# Protoboard.net
KiCad netlist of a schematic drawn in Altium Designer
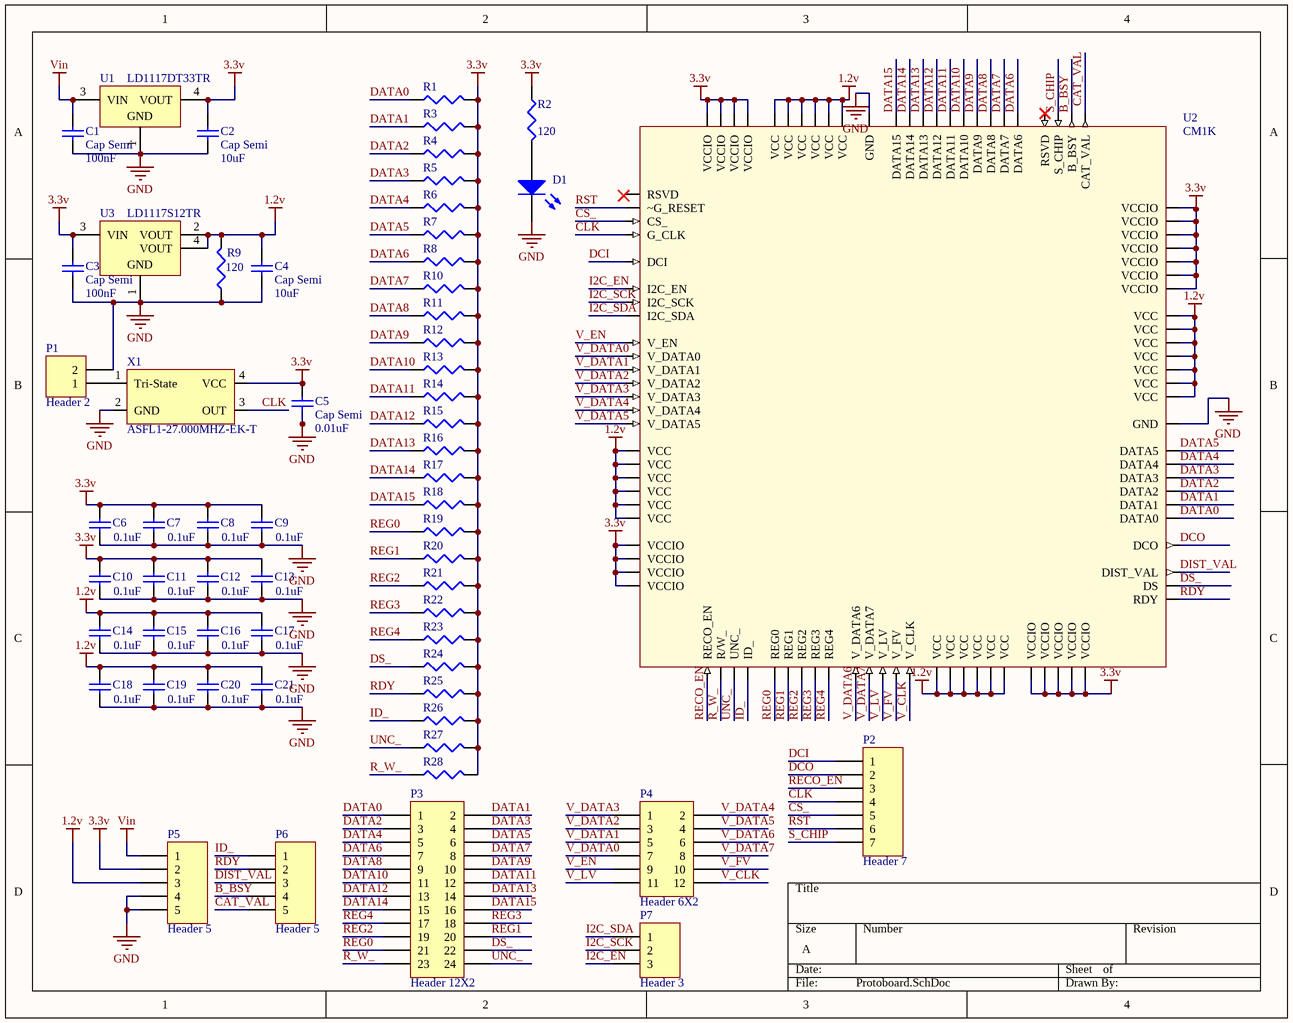
[diagram p0: Protoboard.SchDoc]

(export (version "E")
  (design (tool "Eeschema 10.0.6"))
  (components
    (comp (ref "C1")
      (value "Cap Semi")
      (footprint "1608[0603]")
      (description "Capacitor (Semiconductor SIM Model)")
      (fields (field (name "ALTIUM_VALUE") "100nF") (field (name "PUBLISHER") "Altium Limited"))
      (libsource (lib "Miscellaneous Devices") (part "Cap Semi"))
    )
    (comp (ref "C2")
      (value "Cap Semi")
      (footprint "1608[0603]")
      (description "Capacitor (Semiconductor SIM Model)")
      (fields (field (name "ALTIUM_VALUE") "10uF") (field (name "PUBLISHER") "Altium Limited"))
      (libsource (lib "Miscellaneous Devices") (part "Cap Semi"))
    )
    (comp (ref "C3")
      (value "Cap Semi")
      (footprint "1608[0603]")
      (description "Capacitor (Semiconductor SIM Model)")
      (fields (field (name "ALTIUM_VALUE") "100nF") (field (name "PUBLISHER") "Altium Limited"))
      (libsource (lib "Miscellaneous Devices") (part "Cap Semi"))
    )
    (comp (ref "C4")
      (value "Cap Semi")
      (footprint "1608[0603]")
      (description "Capacitor (Semiconductor SIM Model)")
      (fields (field (name "ALTIUM_VALUE") "10uF") (field (name "PUBLISHER") "Altium Limited"))
      (libsource (lib "Miscellaneous Devices") (part "Cap Semi"))
    )
    (comp (ref "C5")
      (value "Cap Semi")
      (footprint "1608[0603]")
      (description "Capacitor (Semiconductor SIM Model)")
      (fields (field (name "ALTIUM_VALUE") "0.01uF") (field (name "PUBLISHER") "Altium Limited"))
      (libsource (lib "Miscellaneous Devices") (part "Cap Semi"))
    )
    (comp (ref "C6")
      (value "0.1uF")
      (footprint "1608[0603]")
      (description "Capacitor (Semiconductor SIM Model)")
      (fields (field (name "Comment") "Cap Semi") (field (name "PUBLISHER") "Altium Limited"))
      (libsource (lib "Miscellaneous Devices") (part "Cap Semi"))
    )
    (comp (ref "C7")
      (value "0.1uF")
      (footprint "1608[0603]")
      (description "Capacitor (Semiconductor SIM Model)")
      (fields (field (name "Comment") "Cap Semi") (field (name "PUBLISHER") "Altium Limited"))
      (libsource (lib "Miscellaneous Devices") (part "Cap Semi"))
    )
    (comp (ref "C8")
      (value "0.1uF")
      (footprint "1608[0603]")
      (description "Capacitor (Semiconductor SIM Model)")
      (fields (field (name "Comment") "Cap Semi") (field (name "PUBLISHER") "Altium Limited"))
      (libsource (lib "Miscellaneous Devices") (part "Cap Semi"))
    )
    (comp (ref "C9")
      (value "0.1uF")
      (footprint "1608[0603]")
      (description "Capacitor (Semiconductor SIM Model)")
      (fields (field (name "Comment") "Cap Semi") (field (name "PUBLISHER") "Altium Limited"))
      (libsource (lib "Miscellaneous Devices") (part "Cap Semi"))
    )
    (comp (ref "C10")
      (value "0.1uF")
      (footprint "1608[0603]")
      (description "Capacitor (Semiconductor SIM Model)")
      (fields (field (name "Comment") "Cap Semi") (field (name "PUBLISHER") "Altium Limited"))
      (libsource (lib "Miscellaneous Devices") (part "Cap Semi"))
    )
    (comp (ref "C11")
      (value "0.1uF")
      (footprint "1608[0603]")
      (description "Capacitor (Semiconductor SIM Model)")
      (fields (field (name "Comment") "Cap Semi") (field (name "PUBLISHER") "Altium Limited"))
      (libsource (lib "Miscellaneous Devices") (part "Cap Semi"))
    )
    (comp (ref "C12")
      (value "0.1uF")
      (footprint "1608[0603]")
      (description "Capacitor (Semiconductor SIM Model)")
      (fields (field (name "Comment") "Cap Semi") (field (name "PUBLISHER") "Altium Limited"))
      (libsource (lib "Miscellaneous Devices") (part "Cap Semi"))
    )
    (comp (ref "C13")
      (value "0.1uF")
      (footprint "1608[0603]")
      (description "Capacitor (Semiconductor SIM Model)")
      (fields (field (name "Comment") "Cap Semi") (field (name "PUBLISHER") "Altium Limited"))
      (libsource (lib "Miscellaneous Devices") (part "Cap Semi"))
    )
    (comp (ref "C14")
      (value "0.1uF")
      (footprint "1608[0603]")
      (description "Capacitor (Semiconductor SIM Model)")
      (fields (field (name "Comment") "Cap Semi") (field (name "PUBLISHER") "Altium Limited"))
      (libsource (lib "Miscellaneous Devices") (part "Cap Semi"))
    )
    (comp (ref "C15")
      (value "0.1uF")
      (footprint "1608[0603]")
      (description "Capacitor (Semiconductor SIM Model)")
      (fields (field (name "Comment") "Cap Semi") (field (name "PUBLISHER") "Altium Limited"))
      (libsource (lib "Miscellaneous Devices") (part "Cap Semi"))
    )
    (comp (ref "C16")
      (value "0.1uF")
      (footprint "1608[0603]")
      (description "Capacitor (Semiconductor SIM Model)")
      (fields (field (name "Comment") "Cap Semi") (field (name "PUBLISHER") "Altium Limited"))
      (libsource (lib "Miscellaneous Devices") (part "Cap Semi"))
    )
    (comp (ref "C17")
      (value "0.1uF")
      (footprint "1608[0603]")
      (description "Capacitor (Semiconductor SIM Model)")
      (fields (field (name "Comment") "Cap Semi") (field (name "PUBLISHER") "Altium Limited"))
      (libsource (lib "Miscellaneous Devices") (part "Cap Semi"))
    )
    (comp (ref "C18")
      (value "0.1uF")
      (footprint "1608[0603]")
      (description "Capacitor (Semiconductor SIM Model)")
      (fields (field (name "Comment") "Cap Semi") (field (name "PUBLISHER") "Altium Limited"))
      (libsource (lib "Miscellaneous Devices") (part "Cap Semi"))
    )
    (comp (ref "C19")
      (value "0.1uF")
      (footprint "1608[0603]")
      (description "Capacitor (Semiconductor SIM Model)")
      (fields (field (name "Comment") "Cap Semi") (field (name "PUBLISHER") "Altium Limited"))
      (libsource (lib "Miscellaneous Devices") (part "Cap Semi"))
    )
    (comp (ref "C20")
      (value "0.1uF")
      (footprint "1608[0603]")
      (description "Capacitor (Semiconductor SIM Model)")
      (fields (field (name "Comment") "Cap Semi") (field (name "PUBLISHER") "Altium Limited"))
      (libsource (lib "Miscellaneous Devices") (part "Cap Semi"))
    )
    (comp (ref "C21")
      (value "0.1uF")
      (footprint "1608[0603]")
      (description "Capacitor (Semiconductor SIM Model)")
      (fields (field (name "Comment") "Cap Semi") (field (name "PUBLISHER") "Altium Limited"))
      (libsource (lib "Miscellaneous Devices") (part "Cap Semi"))
    )
    (comp (ref "D1")
      (value "150060BS75000")
      (footprint "0603_A")
      (description "SMD mono-color Chip LED, WL-SMCW, Blue")
      (fields (field (name "MANUFACTURER") "Wuerth Elektronik"))
      (libsource (lib "Altium Content Vault") (part "WE-LED_K1A2-2"))
    )
    (comp (ref "P1")
      (value "Header 2")
      (footprint "HDR1X2")
      (description "Header, 2-Pin")
      (fields (field (name "PUBLISHER") "Altium Limited"))
      (libsource (lib "Miscellaneous Connectors") (part "Header 2"))
    )
    (comp (ref "P2")
      (value "Header 7")
      (footprint "HDR1X7")
      (description "Header, 7-Pin")
      (fields (field (name "PUBLISHER") "Altium Limited"))
      (libsource (lib "Miscellaneous Connectors") (part "Header 7"))
    )
    (comp (ref "P3")
      (value "Header 12X2")
      (footprint "HDR2X12")
      (description "Header, 12-Pin, Dual row")
      (fields (field (name "PUBLISHER") "Altium Limited"))
      (libsource (lib "Miscellaneous Connectors") (part "Header 12X2"))
    )
    (comp (ref "P4")
      (value "Header 6X2")
      (footprint "HDR2X6")
      (description "Header, 6-Pin, Dual row")
      (fields (field (name "PUBLISHER") "Altium Limited"))
      (libsource (lib "Miscellaneous Connectors") (part "Header 6X2"))
    )
    (comp (ref "P5")
      (value "Header 5")
      (footprint "HDR1X5")
      (description "Header, 5-Pin")
      (fields (field (name "PUBLISHER") "Altium Limited"))
      (libsource (lib "Miscellaneous Connectors") (part "Header 5"))
    )
    (comp (ref "P6")
      (value "Header 5")
      (footprint "HDR1X5")
      (description "Header, 5-Pin")
      (fields (field (name "PUBLISHER") "Altium Limited"))
      (libsource (lib "Miscellaneous Connectors") (part "Header 5"))
    )
    (comp (ref "P7")
      (value "Header 3")
      (footprint "HDR1X3")
      (description "Header, 3-Pin")
      (fields (field (name "PUBLISHER") "Altium Limited"))
      (libsource (lib "Miscellaneous Connectors") (part "Header 3"))
    )
    (comp (ref "R1")
      (value "Res3")
      (footprint "J1-0603")
      (description "Resistor")
      (fields (field (name "PUBLISHER") "Altium Limited"))
      (libsource (lib "Miscellaneous Devices") (part "Res3"))
    )
    (comp (ref "R2")
      (value "120")
      (footprint "J1-0603")
      (description "Resistor")
      (fields (field (name "Comment") "Res3") (field (name "PUBLISHER") "Altium Limited"))
      (libsource (lib "Miscellaneous Devices") (part "Res3"))
    )
    (comp (ref "R3")
      (value "Res3")
      (footprint "J1-0603")
      (description "Resistor")
      (fields (field (name "PUBLISHER") "Altium Limited"))
      (libsource (lib "Miscellaneous Devices") (part "Res3"))
    )
    (comp (ref "R4")
      (value "Res3")
      (footprint "J1-0603")
      (description "Resistor")
      (fields (field (name "PUBLISHER") "Altium Limited"))
      (libsource (lib "Miscellaneous Devices") (part "Res3"))
    )
    (comp (ref "R5")
      (value "Res3")
      (footprint "J1-0603")
      (description "Resistor")
      (fields (field (name "PUBLISHER") "Altium Limited"))
      (libsource (lib "Miscellaneous Devices") (part "Res3"))
    )
    (comp (ref "R6")
      (value "Res3")
      (footprint "J1-0603")
      (description "Resistor")
      (fields (field (name "PUBLISHER") "Altium Limited"))
      (libsource (lib "Miscellaneous Devices") (part "Res3"))
    )
    (comp (ref "R7")
      (value "Res3")
      (footprint "J1-0603")
      (description "Resistor")
      (fields (field (name "PUBLISHER") "Altium Limited"))
      (libsource (lib "Miscellaneous Devices") (part "Res3"))
    )
    (comp (ref "R8")
      (value "Res3")
      (footprint "J1-0603")
      (description "Resistor")
      (fields (field (name "PUBLISHER") "Altium Limited"))
      (libsource (lib "Miscellaneous Devices") (part "Res3"))
    )
    (comp (ref "R9")
      (value "120")
      (footprint "J1-0603")
      (description "Resistor")
      (fields (field (name "Comment") "Res3") (field (name "PUBLISHER") "Altium Limited"))
      (libsource (lib "Miscellaneous Devices") (part "Res3"))
    )
    (comp (ref "R10")
      (value "Res3")
      (footprint "J1-0603")
      (description "Resistor")
      (fields (field (name "PUBLISHER") "Altium Limited"))
      (libsource (lib "Miscellaneous Devices") (part "Res3"))
    )
    (comp (ref "R11")
      (value "Res3")
      (footprint "J1-0603")
      (description "Resistor")
      (fields (field (name "PUBLISHER") "Altium Limited"))
      (libsource (lib "Miscellaneous Devices") (part "Res3"))
    )
    (comp (ref "R12")
      (value "Res3")
      (footprint "J1-0603")
      (description "Resistor")
      (fields (field (name "PUBLISHER") "Altium Limited"))
      (libsource (lib "Miscellaneous Devices") (part "Res3"))
    )
    (comp (ref "R13")
      (value "Res3")
      (footprint "J1-0603")
      (description "Resistor")
      (fields (field (name "PUBLISHER") "Altium Limited"))
      (libsource (lib "Miscellaneous Devices") (part "Res3"))
    )
    (comp (ref "R14")
      (value "Res3")
      (footprint "J1-0603")
      (description "Resistor")
      (fields (field (name "PUBLISHER") "Altium Limited"))
      (libsource (lib "Miscellaneous Devices") (part "Res3"))
    )
    (comp (ref "R15")
      (value "Res3")
      (footprint "J1-0603")
      (description "Resistor")
      (fields (field (name "PUBLISHER") "Altium Limited"))
      (libsource (lib "Miscellaneous Devices") (part "Res3"))
    )
    (comp (ref "R16")
      (value "Res3")
      (footprint "J1-0603")
      (description "Resistor")
      (fields (field (name "PUBLISHER") "Altium Limited"))
      (libsource (lib "Miscellaneous Devices") (part "Res3"))
    )
    (comp (ref "R17")
      (value "Res3")
      (footprint "J1-0603")
      (description "Resistor")
      (fields (field (name "PUBLISHER") "Altium Limited"))
      (libsource (lib "Miscellaneous Devices") (part "Res3"))
    )
    (comp (ref "R18")
      (value "Res3")
      (footprint "J1-0603")
      (description "Resistor")
      (fields (field (name "PUBLISHER") "Altium Limited"))
      (libsource (lib "Miscellaneous Devices") (part "Res3"))
    )
    (comp (ref "R19")
      (value "Res3")
      (footprint "J1-0603")
      (description "Resistor")
      (fields (field (name "PUBLISHER") "Altium Limited"))
      (libsource (lib "Miscellaneous Devices") (part "Res3"))
    )
    (comp (ref "R20")
      (value "Res3")
      (footprint "J1-0603")
      (description "Resistor")
      (fields (field (name "PUBLISHER") "Altium Limited"))
      (libsource (lib "Miscellaneous Devices") (part "Res3"))
    )
    (comp (ref "R21")
      (value "Res3")
      (footprint "J1-0603")
      (description "Resistor")
      (fields (field (name "PUBLISHER") "Altium Limited"))
      (libsource (lib "Miscellaneous Devices") (part "Res3"))
    )
    (comp (ref "R22")
      (value "Res3")
      (footprint "J1-0603")
      (description "Resistor")
      (fields (field (name "PUBLISHER") "Altium Limited"))
      (libsource (lib "Miscellaneous Devices") (part "Res3"))
    )
    (comp (ref "R23")
      (value "Res3")
      (footprint "J1-0603")
      (description "Resistor")
      (fields (field (name "PUBLISHER") "Altium Limited"))
      (libsource (lib "Miscellaneous Devices") (part "Res3"))
    )
    (comp (ref "R24")
      (value "Res3")
      (footprint "J1-0603")
      (description "Resistor")
      (fields (field (name "PUBLISHER") "Altium Limited"))
      (libsource (lib "Miscellaneous Devices") (part "Res3"))
    )
    (comp (ref "R25")
      (value "Res3")
      (footprint "J1-0603")
      (description "Resistor")
      (fields (field (name "PUBLISHER") "Altium Limited"))
      (libsource (lib "Miscellaneous Devices") (part "Res3"))
    )
    (comp (ref "R26")
      (value "Res3")
      (footprint "J1-0603")
      (description "Resistor")
      (fields (field (name "PUBLISHER") "Altium Limited"))
      (libsource (lib "Miscellaneous Devices") (part "Res3"))
    )
    (comp (ref "R27")
      (value "Res3")
      (footprint "J1-0603")
      (description "Resistor")
      (fields (field (name "PUBLISHER") "Altium Limited"))
      (libsource (lib "Miscellaneous Devices") (part "Res3"))
    )
    (comp (ref "R28")
      (value "Res3")
      (footprint "J1-0603")
      (description "Resistor")
      (fields (field (name "PUBLISHER") "Altium Limited"))
      (libsource (lib "Miscellaneous Devices") (part "Res3"))
    )
    (comp (ref "U1")
      (value "LD1117DT33TR")
      (footprint "TO-252_N")
      (description "Fixed Low Drop Positive Voltage Regulator, 3.3V, 3-Pin DPAK, Tape and Reel")
      (libsource (lib "Altium Content Vault") (part "PM-REG-LD1117-SOT3"))
    )
    (comp (ref "U2")
      (value "CM1K")
      (footprint "TSQFP50P1600X1600X120-100N")
      (libsource (lib "CM1K") (part "CM1K"))
    )
    (comp (ref "U3")
      (value "LD1117S12TR")
      (footprint "SOT-223_M")
      (description "Fixed Low Drop Positive Voltage Regulator, 1.2V, 4-Pin SOT-223, Tape and Reel")
      (libsource (lib "Altium Content Vault") (part "PM-REG-LD1117-SOT4"))
    )
    (comp (ref "X1")
      (value "ASFL1-27.000MHZ-EK-T")
      (footprint "Oscillator")
      (libsource (lib "Oscillator") (part "Component_1"))
    )
  )
  (nets
    (net (code "1") (name "/B_BSY") (class "Default")
      (node (ref "P6") (pin "4") (pinfunction "4_4") (pintype "passive"))
      (node (ref "U2") (pin "97") (pinfunction "B_BSY_97") (pintype "output"))
    )
    (net (code "2") (name "/CAT_VAL") (class "Default")
      (node (ref "P6") (pin "5") (pinfunction "5_5") (pintype "passive"))
      (node (ref "U2") (pin "96") (pinfunction "CAT_VAL_96") (pintype "output"))
    )
    (net (code "3") (name "/CLK") (class "Default")
      (node (ref "P2") (pin "4") (pinfunction "4_4") (pintype "passive"))
      (node (ref "U2") (pin "8") (pinfunction "G_CLK_8") (pintype "input"))
      (node (ref "X1") (pin "3") (pinfunction "OUT_3") (pintype "passive"))
    )
    (net (code "4") (name "/CS_") (class "Default")
      (node (ref "P2") (pin "5") (pinfunction "5_5") (pintype "passive"))
      (node (ref "U2") (pin "6") (pinfunction "CS__6") (pintype "input"))
    )
    (net (code "5") (name "/DATA0") (class "Default")
      (node (ref "P3") (pin "1") (pinfunction "1_1") (pintype "passive"))
      (node (ref "R1") (pin "1") (pinfunction "1_1") (pintype "passive"))
      (node (ref "U2") (pin "63") (pinfunction "DATA0_63") (pintype "bidirectional"))
    )
    (net (code "6") (name "/DATA1") (class "Default")
      (node (ref "P3") (pin "2") (pinfunction "2_2") (pintype "passive"))
      (node (ref "R3") (pin "1") (pinfunction "1_1") (pintype "passive"))
      (node (ref "U2") (pin "65") (pinfunction "DATA1_65") (pintype "bidirectional"))
    )
    (net (code "7") (name "/DATA2") (class "Default")
      (node (ref "P3") (pin "3") (pinfunction "3_3") (pintype "passive"))
      (node (ref "R4") (pin "1") (pinfunction "1_1") (pintype "passive"))
      (node (ref "U2") (pin "67") (pinfunction "DATA2_67") (pintype "bidirectional"))
    )
    (net (code "8") (name "/DATA3") (class "Default")
      (node (ref "P3") (pin "4") (pinfunction "4_4") (pintype "passive"))
      (node (ref "R5") (pin "1") (pinfunction "1_1") (pintype "passive"))
      (node (ref "U2") (pin "69") (pinfunction "DATA3_69") (pintype "bidirectional"))
    )
    (net (code "9") (name "/DATA4") (class "Default")
      (node (ref "P3") (pin "5") (pinfunction "5_5") (pintype "passive"))
      (node (ref "R6") (pin "1") (pinfunction "1_1") (pintype "passive"))
      (node (ref "U2") (pin "73") (pinfunction "DATA4_73") (pintype "bidirectional"))
    )
    (net (code "10") (name "/DATA5") (class "Default")
      (node (ref "P3") (pin "6") (pinfunction "6_6") (pintype "passive"))
      (node (ref "R7") (pin "1") (pinfunction "1_1") (pintype "passive"))
      (node (ref "U2") (pin "75") (pinfunction "DATA5_75") (pintype "bidirectional"))
    )
    (net (code "11") (name "/DATA6") (class "Default")
      (node (ref "P3") (pin "7") (pinfunction "7_7") (pintype "passive"))
      (node (ref "R8") (pin "1") (pinfunction "1_1") (pintype "passive"))
      (node (ref "U2") (pin "76") (pinfunction "DATA6_76") (pintype "bidirectional"))
    )
    (net (code "12") (name "/DATA7") (class "Default")
      (node (ref "P3") (pin "8") (pinfunction "8_8") (pintype "passive"))
      (node (ref "R10") (pin "1") (pinfunction "1_1") (pintype "passive"))
      (node (ref "U2") (pin "78") (pinfunction "DATA7_78") (pintype "bidirectional"))
    )
    (net (code "13") (name "/DATA8") (class "Default")
      (node (ref "P3") (pin "9") (pinfunction "9_9") (pintype "passive"))
      (node (ref "R11") (pin "1") (pinfunction "1_1") (pintype "passive"))
      (node (ref "U2") (pin "80") (pinfunction "DATA8_80") (pintype "bidirectional"))
    )
    (net (code "14") (name "/DATA9") (class "Default")
      (node (ref "P3") (pin "10") (pinfunction "10_10") (pintype "passive"))
      (node (ref "R12") (pin "1") (pinfunction "1_1") (pintype "passive"))
      (node (ref "U2") (pin "81") (pinfunction "DATA9_81") (pintype "bidirectional"))
    )
    (net (code "15") (name "/DATA10") (class "Default")
      (node (ref "P3") (pin "11") (pinfunction "11_11") (pintype "passive"))
      (node (ref "R13") (pin "1") (pinfunction "1_1") (pintype "passive"))
      (node (ref "U2") (pin "84") (pinfunction "DATA10_84") (pintype "bidirectional"))
    )
    (net (code "16") (name "/DATA11") (class "Default")
      (node (ref "P3") (pin "12") (pinfunction "12_12") (pintype "passive"))
      (node (ref "R14") (pin "1") (pinfunction "1_1") (pintype "passive"))
      (node (ref "U2") (pin "87") (pinfunction "DATA11_87") (pintype "bidirectional"))
    )
    (net (code "17") (name "/DATA12") (class "Default")
      (node (ref "P3") (pin "13") (pinfunction "13_13") (pintype "passive"))
      (node (ref "R15") (pin "1") (pinfunction "1_1") (pintype "passive"))
      (node (ref "U2") (pin "88") (pinfunction "DATA12_88") (pintype "bidirectional"))
    )
    (net (code "18") (name "/DATA13") (class "Default")
      (node (ref "P3") (pin "14") (pinfunction "14_14") (pintype "passive"))
      (node (ref "R16") (pin "1") (pinfunction "1_1") (pintype "passive"))
      (node (ref "U2") (pin "91") (pinfunction "DATA13_91") (pintype "bidirectional"))
    )
    (net (code "19") (name "/DATA14") (class "Default")
      (node (ref "P3") (pin "15") (pinfunction "15_15") (pintype "passive"))
      (node (ref "R17") (pin "1") (pinfunction "1_1") (pintype "passive"))
      (node (ref "U2") (pin "93") (pinfunction "DATA14_93") (pintype "bidirectional"))
    )
    (net (code "20") (name "/DATA15") (class "Default")
      (node (ref "P3") (pin "16") (pinfunction "16_16") (pintype "passive"))
      (node (ref "R18") (pin "1") (pinfunction "1_1") (pintype "passive"))
      (node (ref "U2") (pin "95") (pinfunction "DATA15_95") (pintype "bidirectional"))
    )
    (net (code "21") (name "/DCI") (class "Default")
      (node (ref "P2") (pin "1") (pinfunction "1_1") (pintype "passive"))
      (node (ref "U2") (pin "13") (pinfunction "DCI_13") (pintype "input"))
    )
    (net (code "22") (name "/DCO") (class "Default")
      (node (ref "P2") (pin "2") (pinfunction "2_2") (pintype "passive"))
      (node (ref "U2") (pin "62") (pinfunction "DCO_62") (pintype "output"))
    )
    (net (code "23") (name "/DIST_VAL") (class "Default")
      (node (ref "P6") (pin "3") (pinfunction "3_3") (pintype "passive"))
      (node (ref "U2") (pin "58") (pinfunction "DIST_VAL_58") (pintype "output"))
    )
    (net (code "24") (name "/DS_") (class "Default")
      (node (ref "P3") (pin "22") (pinfunction "22_22") (pintype "passive"))
      (node (ref "R24") (pin "1") (pinfunction "1_1") (pintype "passive"))
      (node (ref "U2") (pin "53") (pinfunction "DS_53") (pintype "bidirectional"))
    )
    (net (code "25") (name "/I2C_EN") (class "Default")
      (node (ref "P7") (pin "3") (pinfunction "3_3") (pintype "passive"))
      (node (ref "U2") (pin "5") (pinfunction "I2C_EN_5") (pintype "input"))
    )
    (net (code "26") (name "/I2C_SCK") (class "Default")
      (node (ref "P7") (pin "2") (pinfunction "2_2") (pintype "passive"))
      (node (ref "U2") (pin "10") (pinfunction "I2C_SCK_10") (pintype "input"))
    )
    (net (code "27") (name "/I2C_SDA") (class "Default")
      (node (ref "P7") (pin "1") (pinfunction "1_1") (pintype "passive"))
      (node (ref "U2") (pin "15") (pinfunction "I2C_SDA_15") (pintype "bidirectional"))
    )
    (net (code "28") (name "/ID_") (class "Default")
      (node (ref "P6") (pin "1") (pinfunction "1_1") (pintype "passive"))
      (node (ref "R26") (pin "1") (pinfunction "1_1") (pintype "passive"))
      (node (ref "U2") (pin "50") (pinfunction "ID__50") (pintype "bidirectional"))
    )
    (net (code "29") (name "/RDY") (class "Default")
      (node (ref "P6") (pin "2") (pinfunction "2_2") (pintype "passive"))
      (node (ref "R25") (pin "1") (pinfunction "1_1") (pintype "passive"))
      (node (ref "U2") (pin "52") (pinfunction "RDY_52") (pintype "bidirectional"))
    )
    (net (code "30") (name "/RECO_EN") (class "Default")
      (node (ref "P2") (pin "3") (pinfunction "3_3") (pintype "passive"))
      (node (ref "U2") (pin "46") (pinfunction "RECO_EN_46") (pintype "input"))
    )
    (net (code "31") (name "/REG0") (class "Default")
      (node (ref "P3") (pin "21") (pinfunction "21_21") (pintype "passive"))
      (node (ref "R19") (pin "1") (pinfunction "1_1") (pintype "passive"))
      (node (ref "U2") (pin "36") (pinfunction "REG0_36") (pintype "bidirectional"))
    )
    (net (code "32") (name "/REG1") (class "Default")
      (node (ref "P3") (pin "20") (pinfunction "20_20") (pintype "passive"))
      (node (ref "R20") (pin "1") (pinfunction "1_1") (pintype "passive"))
      (node (ref "U2") (pin "37") (pinfunction "REG1_37") (pintype "bidirectional"))
    )
    (net (code "33") (name "/REG2") (class "Default")
      (node (ref "P3") (pin "19") (pinfunction "19_19") (pintype "passive"))
      (node (ref "R21") (pin "1") (pinfunction "1_1") (pintype "passive"))
      (node (ref "U2") (pin "40") (pinfunction "REG2_40") (pintype "bidirectional"))
    )
    (net (code "34") (name "/REG3") (class "Default")
      (node (ref "P3") (pin "18") (pinfunction "18_18") (pintype "passive"))
      (node (ref "R22") (pin "1") (pinfunction "1_1") (pintype "passive"))
      (node (ref "U2") (pin "41") (pinfunction "REG3_41") (pintype "bidirectional"))
    )
    (net (code "35") (name "/REG4") (class "Default")
      (node (ref "P3") (pin "17") (pinfunction "17_17") (pintype "passive"))
      (node (ref "R23") (pin "1") (pinfunction "1_1") (pintype "passive"))
      (node (ref "U2") (pin "43") (pinfunction "REG4_43") (pintype "bidirectional"))
    )
    (net (code "36") (name "/RST") (class "Default")
      (node (ref "P2") (pin "6") (pinfunction "6_6") (pintype "passive"))
      (node (ref "U2") (pin "3") (pinfunction "~G_RESET_3") (pintype "bidirectional"))
    )
    (net (code "37") (name "/R_W_") (class "Default")
      (node (ref "P3") (pin "23") (pinfunction "23_23") (pintype "passive"))
      (node (ref "R28") (pin "1") (pinfunction "1_1") (pintype "passive"))
      (node (ref "U2") (pin "47") (pinfunction "R/W__47") (pintype "bidirectional"))
    )
    (net (code "38") (name "/S_CHIP") (class "Default")
      (node (ref "P2") (pin "7") (pinfunction "7_7") (pintype "passive"))
      (node (ref "U2") (pin "99") (pinfunction "S_CHIP_99") (pintype "input"))
    )
    (net (code "39") (name "/UNC_") (class "Default")
      (node (ref "P3") (pin "24") (pinfunction "24_24") (pintype "passive"))
      (node (ref "R27") (pin "1") (pinfunction "1_1") (pintype "passive"))
      (node (ref "U2") (pin "49") (pinfunction "UNC__49") (pintype "bidirectional"))
    )
    (net (code "40") (name "/V_CLK") (class "Default")
      (node (ref "P4") (pin "12") (pinfunction "12_12") (pintype "passive"))
      (node (ref "U2") (pin "33") (pinfunction "V_CLK_33") (pintype "input"))
    )
    (net (code "41") (name "/V_DATA0") (class "Default")
      (node (ref "P4") (pin "7") (pinfunction "7_7") (pintype "passive"))
      (node (ref "U2") (pin "18") (pinfunction "V_DATA0_18") (pintype "input"))
    )
    (net (code "42") (name "/V_DATA1") (class "Default")
      (node (ref "P4") (pin "5") (pinfunction "5_5") (pintype "passive"))
      (node (ref "U2") (pin "19") (pinfunction "V_DATA1_19") (pintype "input"))
    )
    (net (code "43") (name "/V_DATA2") (class "Default")
      (node (ref "P4") (pin "3") (pinfunction "3_3") (pintype "passive"))
      (node (ref "U2") (pin "21") (pinfunction "V_DATA2_21") (pintype "input"))
    )
    (net (code "44") (name "/V_DATA3") (class "Default")
      (node (ref "P4") (pin "1") (pinfunction "1_1") (pintype "passive"))
      (node (ref "U2") (pin "23") (pinfunction "V_DATA3_23") (pintype "input"))
    )
    (net (code "45") (name "/V_DATA4") (class "Default")
      (node (ref "P4") (pin "2") (pinfunction "2_2") (pintype "passive"))
      (node (ref "U2") (pin "24") (pinfunction "V_DATA4_24") (pintype "input"))
    )
    (net (code "46") (name "/V_DATA5") (class "Default")
      (node (ref "P4") (pin "4") (pinfunction "4_4") (pintype "passive"))
      (node (ref "U2") (pin "25") (pinfunction "V_DATA5_25") (pintype "input"))
    )
    (net (code "47") (name "/V_DATA6") (class "Default")
      (node (ref "P4") (pin "6") (pinfunction "6_6") (pintype "passive"))
      (node (ref "U2") (pin "26") (pinfunction "V_DATA6_26") (pintype "input"))
    )
    (net (code "48") (name "/V_DATA7") (class "Default")
      (node (ref "P4") (pin "8") (pinfunction "8_8") (pintype "passive"))
      (node (ref "U2") (pin "27") (pinfunction "V_DATA7_27") (pintype "input"))
    )
    (net (code "49") (name "/V_EN") (class "Default")
      (node (ref "P4") (pin "9") (pinfunction "9_9") (pintype "passive"))
      (node (ref "U2") (pin "16") (pinfunction "V_EN_16") (pintype "input"))
    )
    (net (code "50") (name "/V_FV") (class "Default")
      (node (ref "P4") (pin "10") (pinfunction "10_10") (pintype "passive"))
      (node (ref "U2") (pin "30") (pinfunction "V_FV_30") (pintype "input"))
    )
    (net (code "51") (name "/V_LV") (class "Default")
      (node (ref "P4") (pin "11") (pinfunction "11_11") (pintype "passive"))
      (node (ref "U2") (pin "28") (pinfunction "V_LV_28") (pintype "input"))
    )
    (net (code "52") (name "1.2v") (class "Default")
      (node (ref "C14") (pin "2") (pinfunction "2_2") (pintype "passive"))
      (node (ref "C15") (pin "2") (pinfunction "2_2") (pintype "passive"))
      (node (ref "C16") (pin "2") (pinfunction "2_2") (pintype "passive"))
      (node (ref "C17") (pin "2") (pinfunction "2_2") (pintype "passive"))
      (node (ref "C18") (pin "2") (pinfunction "2_2") (pintype "passive"))
      (node (ref "C19") (pin "2") (pinfunction "2_2") (pintype "passive"))
      (node (ref "C20") (pin "2") (pinfunction "2_2") (pintype "passive"))
      (node (ref "C21") (pin "2") (pinfunction "2_2") (pintype "passive"))
      (node (ref "C4") (pin "2") (pinfunction "2_2") (pintype "passive"))
      (node (ref "P5") (pin "3") (pinfunction "3_3") (pintype "passive"))
      (node (ref "R9") (pin "2") (pinfunction "2_2") (pintype "passive"))
      (node (ref "U2") (pin "11") (pinfunction "VCC_11") (pintype "power_in"))
      (node (ref "U2") (pin "14") (pinfunction "VCC_14") (pintype "power_in"))
      (node (ref "U2") (pin "17") (pinfunction "VCC_17") (pintype "power_in"))
      (node (ref "U2") (pin "20") (pinfunction "VCC_20") (pintype "power_in"))
      (node (ref "U2") (pin "22") (pinfunction "VCC_22") (pintype "power_in"))
      (node (ref "U2") (pin "29") (pinfunction "VCC_29") (pintype "power_in"))
      (node (ref "U2") (pin "31") (pinfunction "VCC_31") (pintype "power_in"))
      (node (ref "U2") (pin "35") (pinfunction "VCC_35") (pintype "power_in"))
      (node (ref "U2") (pin "38") (pinfunction "VCC_38") (pintype "power_in"))
      (node (ref "U2") (pin "4") (pinfunction "VCC_4") (pintype "power_in"))
      (node (ref "U2") (pin "42") (pinfunction "VCC_42") (pintype "power_in"))
      (node (ref "U2") (pin "45") (pinfunction "VCC_45") (pintype "power_in"))
      (node (ref "U2") (pin "55") (pinfunction "VCC_55") (pintype "power_in"))
      (node (ref "U2") (pin "56") (pinfunction "VCC_56") (pintype "power_in"))
      (node (ref "U2") (pin "60") (pinfunction "VCC_60") (pintype "power_in"))
      (node (ref "U2") (pin "61") (pinfunction "VCC_61") (pintype "power_in"))
      (node (ref "U2") (pin "66") (pinfunction "VCC_66") (pintype "power_in"))
      (node (ref "U2") (pin "70") (pinfunction "VCC_70") (pintype "power_in"))
      (node (ref "U2") (pin "72") (pinfunction "VCC_72") (pintype "power_in"))
      (node (ref "U2") (pin "83") (pinfunction "VCC_83") (pintype "power_in"))
      (node (ref "U2") (pin "85") (pinfunction "VCC_85") (pintype "power_in"))
      (node (ref "U2") (pin "89") (pinfunction "VCC_89") (pintype "power_in"))
      (node (ref "U2") (pin "92") (pinfunction "VCC_92") (pintype "power_in"))
      (node (ref "U2") (pin "94") (pinfunction "VCC_94") (pintype "power_in"))
      (node (ref "U2") (pin "98") (pinfunction "VCC_98") (pintype "power_in"))
      (node (ref "U3") (pin "2") (pinfunction "VOUT_2") (pintype "power_in"))
      (node (ref "U3") (pin "4") (pinfunction "VOUT_4") (pintype "power_in"))
    )
    (net (code "53") (name "3.3v") (class "Default")
      (node (ref "C10") (pin "2") (pinfunction "2_2") (pintype "passive"))
      (node (ref "C11") (pin "2") (pinfunction "2_2") (pintype "passive"))
      (node (ref "C12") (pin "2") (pinfunction "2_2") (pintype "passive"))
      (node (ref "C13") (pin "2") (pinfunction "2_2") (pintype "passive"))
      (node (ref "C2") (pin "2") (pinfunction "2_2") (pintype "passive"))
      (node (ref "C3") (pin "2") (pinfunction "2_2") (pintype "passive"))
      (node (ref "C5") (pin "2") (pinfunction "2_2") (pintype "passive"))
      (node (ref "C6") (pin "2") (pinfunction "2_2") (pintype "passive"))
      (node (ref "C7") (pin "2") (pinfunction "2_2") (pintype "passive"))
      (node (ref "C8") (pin "2") (pinfunction "2_2") (pintype "passive"))
      (node (ref "C9") (pin "2") (pinfunction "2_2") (pintype "passive"))
      (node (ref "P5") (pin "2") (pinfunction "2_2") (pintype "passive"))
      (node (ref "R1") (pin "2") (pinfunction "2_2") (pintype "passive"))
      (node (ref "R10") (pin "2") (pinfunction "2_2") (pintype "passive"))
      (node (ref "R11") (pin "2") (pinfunction "2_2") (pintype "passive"))
      (node (ref "R12") (pin "2") (pinfunction "2_2") (pintype "passive"))
      (node (ref "R13") (pin "2") (pinfunction "2_2") (pintype "passive"))
      (node (ref "R14") (pin "2") (pinfunction "2_2") (pintype "passive"))
      (node (ref "R15") (pin "2") (pinfunction "2_2") (pintype "passive"))
      (node (ref "R16") (pin "2") (pinfunction "2_2") (pintype "passive"))
      (node (ref "R17") (pin "2") (pinfunction "2_2") (pintype "passive"))
      (node (ref "R18") (pin "2") (pinfunction "2_2") (pintype "passive"))
      (node (ref "R19") (pin "2") (pinfunction "2_2") (pintype "passive"))
      (node (ref "R2") (pin "1") (pinfunction "1_1") (pintype "passive"))
      (node (ref "R20") (pin "2") (pinfunction "2_2") (pintype "passive"))
      (node (ref "R21") (pin "2") (pinfunction "2_2") (pintype "passive"))
      (node (ref "R22") (pin "2") (pinfunction "2_2") (pintype "passive"))
      (node (ref "R23") (pin "2") (pinfunction "2_2") (pintype "passive"))
      (node (ref "R24") (pin "2") (pinfunction "2_2") (pintype "passive"))
      (node (ref "R25") (pin "2") (pinfunction "2_2") (pintype "passive"))
      (node (ref "R26") (pin "2") (pinfunction "2_2") (pintype "passive"))
      (node (ref "R27") (pin "2") (pinfunction "2_2") (pintype "passive"))
      (node (ref "R28") (pin "2") (pinfunction "2_2") (pintype "passive"))
      (node (ref "R3") (pin "2") (pinfunction "2_2") (pintype "passive"))
      (node (ref "R4") (pin "2") (pinfunction "2_2") (pintype "passive"))
      (node (ref "R5") (pin "2") (pinfunction "2_2") (pintype "passive"))
      (node (ref "R6") (pin "2") (pinfunction "2_2") (pintype "passive"))
      (node (ref "R7") (pin "2") (pinfunction "2_2") (pintype "passive"))
      (node (ref "R8") (pin "2") (pinfunction "2_2") (pintype "passive"))
      (node (ref "U1") (pin "4") (pinfunction "VOUT_4") (pintype "power_in"))
      (node (ref "U2") (pin "12") (pinfunction "VCCIO_12") (pintype "power_in"))
      (node (ref "U2") (pin "2") (pinfunction "VCCIO_2") (pintype "power_in"))
      (node (ref "U2") (pin "32") (pinfunction "VCCIO_32") (pintype "power_in"))
      (node (ref "U2") (pin "34") (pinfunction "VCCIO_34") (pintype "power_in"))
      (node (ref "U2") (pin "39") (pinfunction "VCCIO_39") (pintype "power_in"))
      (node (ref "U2") (pin "44") (pinfunction "VCCIO_44") (pintype "power_in"))
      (node (ref "U2") (pin "48") (pinfunction "VCCIO_48") (pintype "power_in"))
      (node (ref "U2") (pin "51") (pinfunction "VCCIO_51") (pintype "power_in"))
      (node (ref "U2") (pin "54") (pinfunction "VCCIO_54") (pintype "power_in"))
      (node (ref "U2") (pin "59") (pinfunction "VCCIO_59") (pintype "power_in"))
      (node (ref "U2") (pin "64") (pinfunction "VCCIO_64") (pintype "power_in"))
      (node (ref "U2") (pin "68") (pinfunction "VCCIO_68") (pintype "power_in"))
      (node (ref "U2") (pin "7") (pinfunction "VCCIO_7") (pintype "power_in"))
      (node (ref "U2") (pin "71") (pinfunction "VCCIO_71") (pintype "power_in"))
      (node (ref "U2") (pin "74") (pinfunction "VCCIO_74") (pintype "power_in"))
      (node (ref "U2") (pin "77") (pinfunction "VCCIO_77") (pintype "power_in"))
      (node (ref "U2") (pin "79") (pinfunction "VCCIO_79") (pintype "power_in"))
      (node (ref "U2") (pin "82") (pinfunction "VCCIO_82") (pintype "power_in"))
      (node (ref "U2") (pin "86") (pinfunction "VCCIO_86") (pintype "power_in"))
      (node (ref "U2") (pin "9") (pinfunction "VCCIO_9") (pintype "power_in"))
      (node (ref "U3") (pin "3") (pinfunction "VIN_3") (pintype "power_in"))
      (node (ref "X1") (pin "4") (pinfunction "VCC_4") (pintype "passive"))
    )
    (net (code "54") (name "GND") (class "Default")
      (node (ref "C1") (pin "1") (pinfunction "1_1") (pintype "passive"))
      (node (ref "C10") (pin "1") (pinfunction "1_1") (pintype "passive"))
      (node (ref "C11") (pin "1") (pinfunction "1_1") (pintype "passive"))
      (node (ref "C12") (pin "1") (pinfunction "1_1") (pintype "passive"))
      (node (ref "C13") (pin "1") (pinfunction "1_1") (pintype "passive"))
      (node (ref "C14") (pin "1") (pinfunction "1_1") (pintype "passive"))
      (node (ref "C15") (pin "1") (pinfunction "1_1") (pintype "passive"))
      (node (ref "C16") (pin "1") (pinfunction "1_1") (pintype "passive"))
      (node (ref "C17") (pin "1") (pinfunction "1_1") (pintype "passive"))
      (node (ref "C18") (pin "1") (pinfunction "1_1") (pintype "passive"))
      (node (ref "C19") (pin "1") (pinfunction "1_1") (pintype "passive"))
      (node (ref "C2") (pin "1") (pinfunction "1_1") (pintype "passive"))
      (node (ref "C20") (pin "1") (pinfunction "1_1") (pintype "passive"))
      (node (ref "C21") (pin "1") (pinfunction "1_1") (pintype "passive"))
      (node (ref "C3") (pin "1") (pinfunction "1_1") (pintype "passive"))
      (node (ref "C4") (pin "1") (pinfunction "1_1") (pintype "passive"))
      (node (ref "C5") (pin "1") (pinfunction "1_1") (pintype "passive"))
      (node (ref "C6") (pin "1") (pinfunction "1_1") (pintype "passive"))
      (node (ref "C7") (pin "1") (pinfunction "1_1") (pintype "passive"))
      (node (ref "C8") (pin "1") (pinfunction "1_1") (pintype "passive"))
      (node (ref "C9") (pin "1") (pinfunction "1_1") (pintype "passive"))
      (node (ref "D1") (pin "1") (pinfunction "K_1") (pintype "passive"))
      (node (ref "P1") (pin "2") (pinfunction "2_2") (pintype "passive"))
      (node (ref "P5") (pin "4") (pinfunction "4_4") (pintype "passive"))
      (node (ref "P5") (pin "5") (pinfunction "5_5") (pintype "passive"))
      (node (ref "R9") (pin "1") (pinfunction "1_1") (pintype "passive"))
      (node (ref "U1") (pin "1") (pinfunction "GND_1") (pintype "power_in"))
      (node (ref "U2") (pin "57") (pinfunction "GND_57") (pintype "power_in"))
      (node (ref "U2") (pin "90") (pinfunction "GND_90") (pintype "power_in"))
      (node (ref "U3") (pin "1") (pinfunction "GND_1") (pintype "power_in"))
      (node (ref "X1") (pin "2") (pinfunction "GND_2") (pintype "passive"))
    )
    (net (code "55") (name "Net-(D1-A)") (class "Default")
      (node (ref "D1") (pin "2") (pinfunction "A_2") (pintype "passive"))
      (node (ref "R2") (pin "2") (pinfunction "2_2") (pintype "passive"))
    )
    (net (code "56") (name "Net-(X1-Tri-State)") (class "Default")
      (node (ref "P1") (pin "1") (pinfunction "1_1") (pintype "passive"))
      (node (ref "X1") (pin "1") (pinfunction "Tri-State_1") (pintype "passive"))
    )
    (net (code "57") (name "Vin") (class "Default")
      (node (ref "C1") (pin "2") (pinfunction "2_2") (pintype "passive"))
      (node (ref "P5") (pin "1") (pinfunction "1_1") (pintype "passive"))
      (node (ref "U1") (pin "3") (pinfunction "VIN_3") (pintype "power_in"))
    )
    (net (code "58") (name "unconnected-(U2-RSVD-Pad1)") (class "Default")
      (node (ref "U2") (pin "1") (pinfunction "RSVD_1") (pintype "bidirectional"))
    )
    (net (code "59") (name "unconnected-(U2-RSVD-Pad100)") (class "Default")
      (node (ref "U2") (pin "100") (pinfunction "RSVD_100") (pintype "input+no_connect"))
    )
  )
)
